# sdcard.net
KiCad netlist of a schematic drawn in Altium Designer
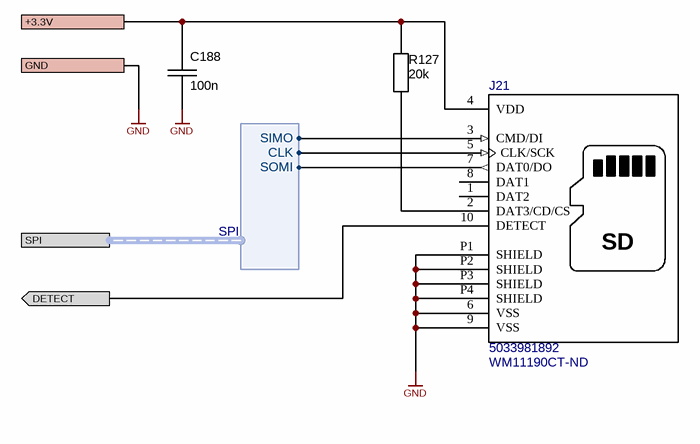
[diagram p0: sdcard.SchDoc]

(export (version "E")
  (design (tool "Eeschema 10.0.6"))
  (components
    (comp (ref "C188")
      (value "100n")
      (footprint "SM/C0402")
      (description "0.1 µF ±10% 25V Ceramic Capacitor X5R 0402 (1005 Metric)")
      (fields (field (name "VOLTAGE") "25V"))
      (libsource (lib "kalios") (part "C"))
    )
    (comp (ref "J21")
      (value "5033981892")
      (footprint "MOLEX_503398-1892")
      (fields (field (name "SUPPLIER PART NUMBER 1") "WM11190CT-ND"))
      (libsource (lib "kalios") (part "CONN SD MOLEX 503398-1892"))
    )
    (comp (ref "R127")
      (value "20k")
      (footprint "SM/R0402")
      (description "20 kOhms ±1% 0.063W, 1/16W Chip Resistor 0402 (1005 Metric) Moisture Resistant Thick Film")
      (libsource (lib "kalios") (part "R"))
    )
  )
  (nets
    (net (code "2") (name "/+3.3V") (class "Default")
      (node (ref "C188") (pin "1") (pintype "passive"))
      (node (ref "J21") (pin "4") (pinfunction "VDD_4") (pintype "power_in"))
      (node (ref "R127") (pin "1") (pintype "passive"))
    )
    (net (code "3") (name "/CLK") (class "Default")
      (node (ref "J21") (pin "5") (pinfunction "CLK/SCK_5") (pintype "input"))
    )
    (net (code "4") (name "/DETECT") (class "Default")
      (node (ref "J21") (pin "10") (pinfunction "DETECT_10") (pintype "passive"))
    )
    (net (code "5") (name "/SIMO") (class "Default")
      (node (ref "J21") (pin "3") (pinfunction "CMD/DI_3") (pintype "input"))
    )
    (net (code "6") (name "/SOMI") (class "Default")
      (node (ref "J21") (pin "7") (pinfunction "DAT0/DO_7") (pintype "output"))
    )
    (net (code "8") (name "GND") (class "Default")
      (node (ref "C188") (pin "2") (pintype "passive"))
      (node (ref "J21") (pin "6") (pinfunction "VSS_6") (pintype "power_in"))
      (node (ref "J21") (pin "9") (pinfunction "VSS_9") (pintype "power_in"))
      (node (ref "J21") (pin "P1") (pinfunction "SHIELD_P1") (pintype "passive"))
      (node (ref "J21") (pin "P2") (pinfunction "SHIELD_P2") (pintype "passive"))
      (node (ref "J21") (pin "P3") (pinfunction "SHIELD_P3") (pintype "passive"))
      (node (ref "J21") (pin "P4") (pinfunction "SHIELD_P4") (pintype "passive"))
    )
    (net (code "9") (name "Net-(J21-DAT3{slash}CD{slash}CS)") (class "Default")
      (node (ref "J21") (pin "2") (pinfunction "DAT3/CD/CS_2") (pintype "passive"))
      (node (ref "R127") (pin "2") (pintype "passive"))
    )
    (net (code "10") (name "unconnected-(J21-DAT1-Pad8)") (class "Default")
      (node (ref "J21") (pin "8") (pinfunction "DAT1_8") (pintype "passive"))
    )
    (net (code "11") (name "unconnected-(J21-DAT2-Pad1)") (class "Default")
      (node (ref "J21") (pin "1") (pinfunction "DAT2_1") (pintype "passive"))
    )
  )
)
